# Switcher.net
KiCad netlist of a schematic drawn in Altium Designer
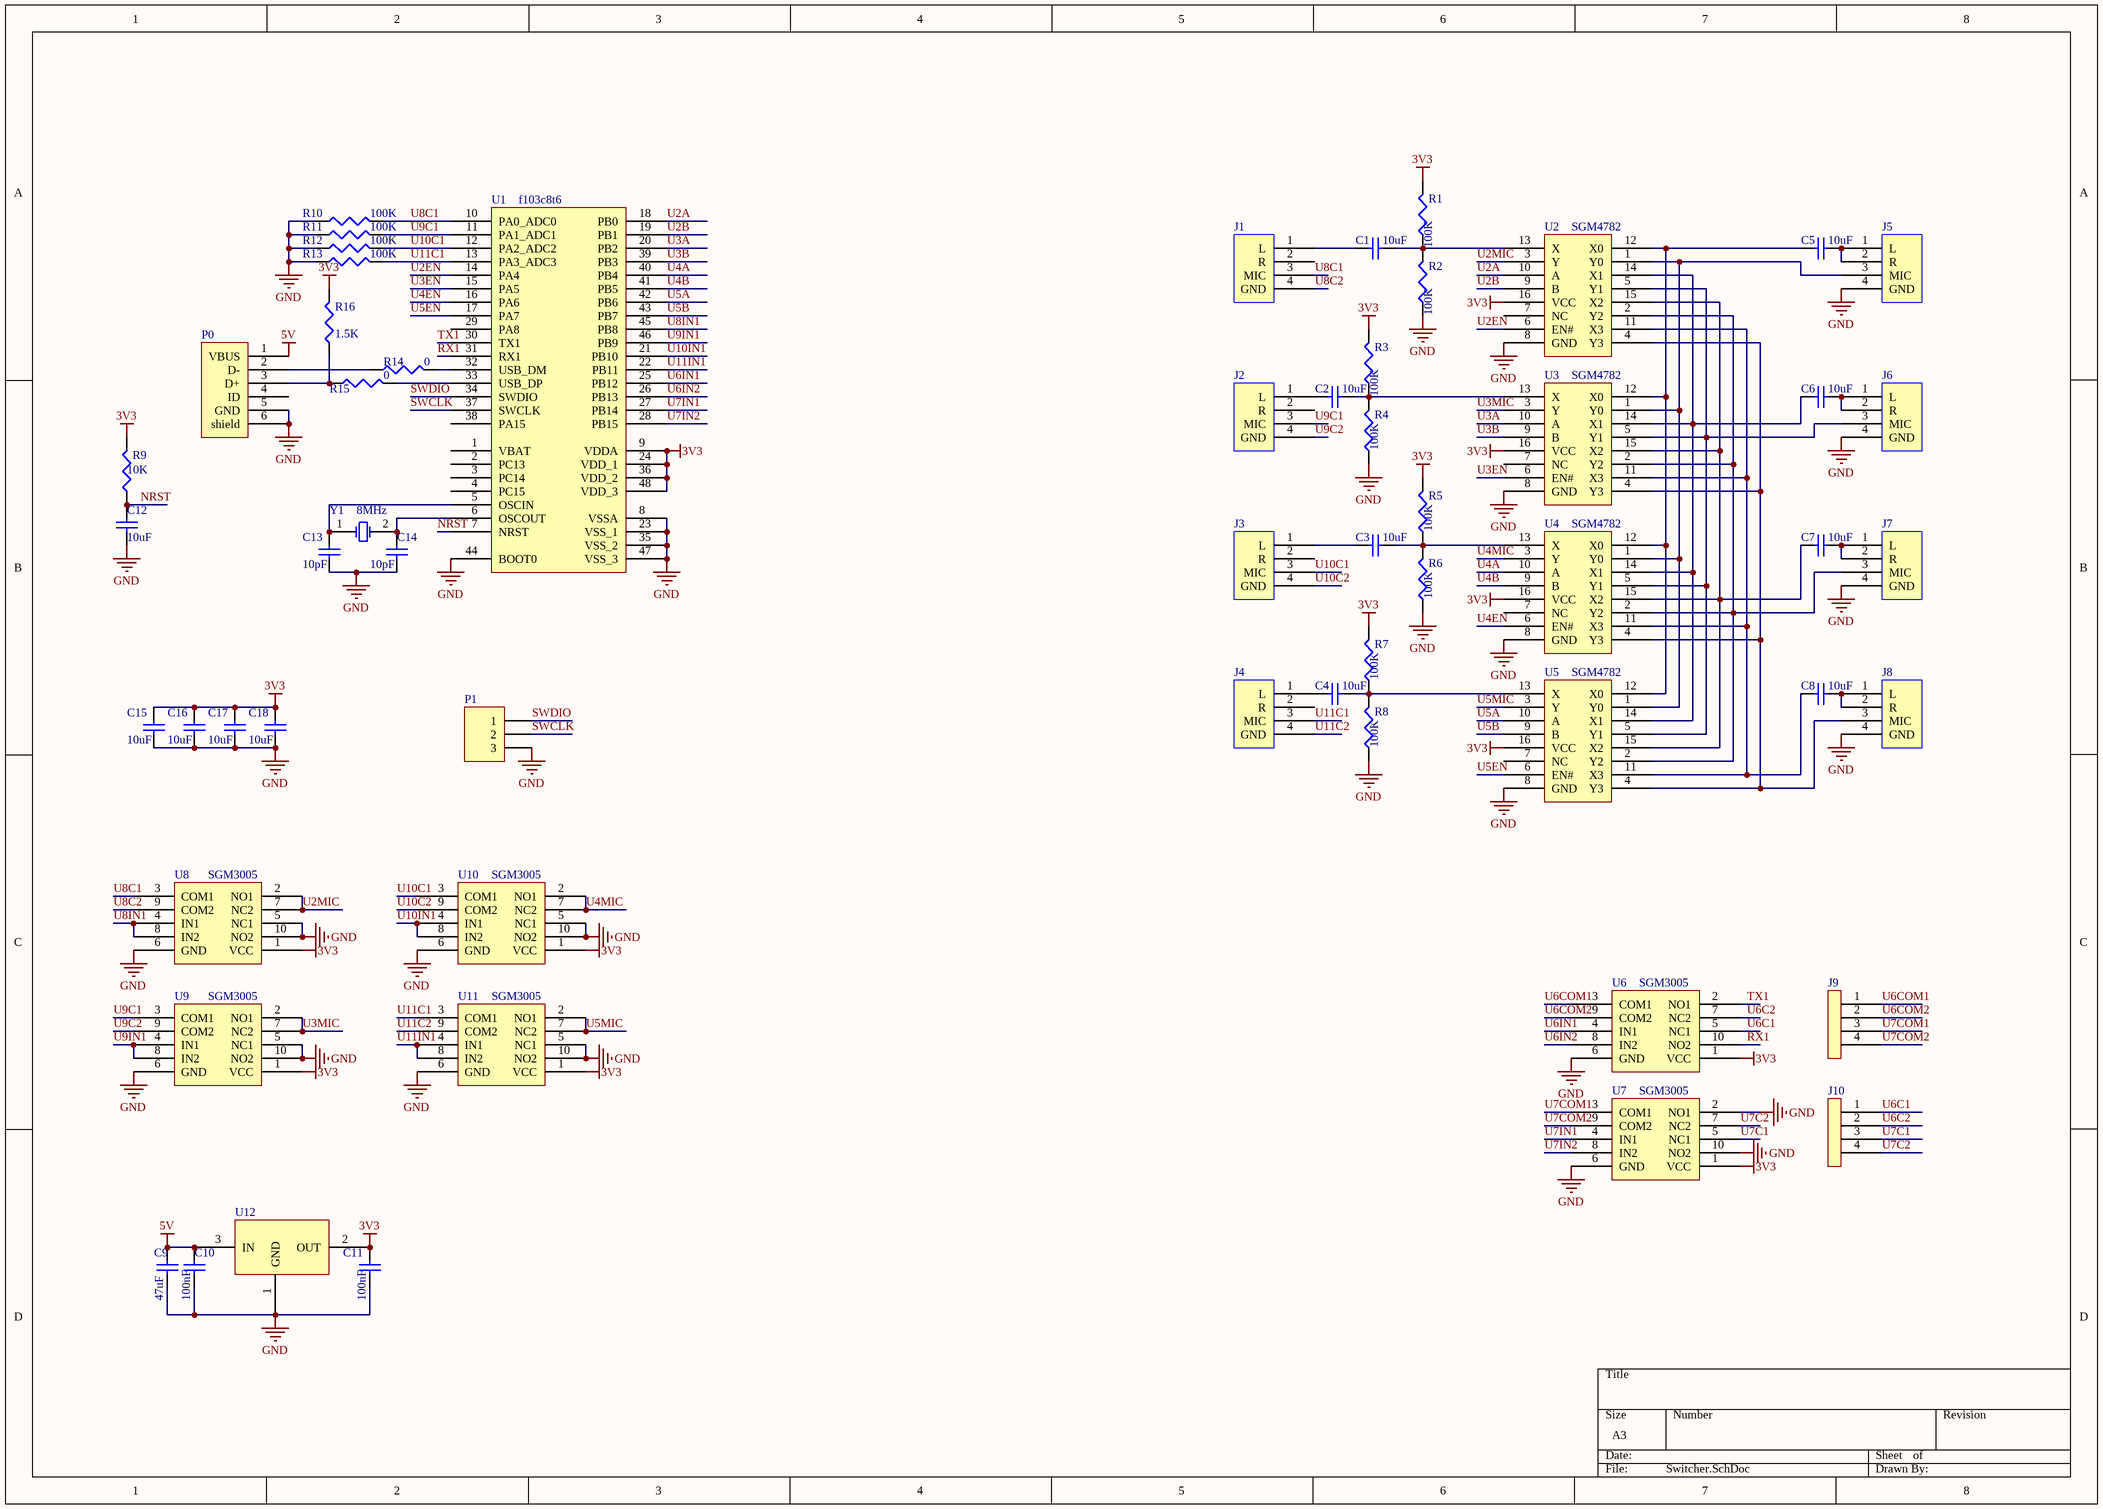
[diagram p0: Switcher.SchDoc]

(export (version "E")
  (design (tool "Eeschema 10.0.6"))
  (components
    (comp (ref "C1")
      (value "10uF")
      (footprint "1608(0603C)")
      (description "Capacitor")
      (fields (field (name "PUBLISHER") "Altium Limited"))
      (libsource (lib "Miscellaneous Devices") (part "Cap"))
    )
    (comp (ref "C2")
      (value "10uF")
      (footprint "1608(0603C)")
      (description "Capacitor")
      (fields (field (name "PUBLISHER") "Altium Limited"))
      (libsource (lib "Miscellaneous Devices") (part "Cap"))
    )
    (comp (ref "C3")
      (value "10uF")
      (footprint "1608(0603C)")
      (description "Capacitor")
      (fields (field (name "PUBLISHER") "Altium Limited"))
      (libsource (lib "Miscellaneous Devices") (part "Cap"))
    )
    (comp (ref "C4")
      (value "10uF")
      (footprint "1608(0603C)")
      (description "Capacitor")
      (fields (field (name "PUBLISHER") "Altium Limited"))
      (libsource (lib "Miscellaneous Devices") (part "Cap"))
    )
    (comp (ref "C5")
      (value "10uF")
      (footprint "1608(0603C)")
      (description "Capacitor")
      (fields (field (name "PUBLISHER") "Altium Limited"))
      (libsource (lib "Miscellaneous Devices") (part "Cap"))
    )
    (comp (ref "C6")
      (value "10uF")
      (footprint "1608(0603C)")
      (description "Capacitor")
      (fields (field (name "PUBLISHER") "Altium Limited"))
      (libsource (lib "Miscellaneous Devices") (part "Cap"))
    )
    (comp (ref "C7")
      (value "10uF")
      (footprint "1608(0603C)")
      (description "Capacitor")
      (fields (field (name "PUBLISHER") "Altium Limited"))
      (libsource (lib "Miscellaneous Devices") (part "Cap"))
    )
    (comp (ref "C8")
      (value "10uF")
      (footprint "1608(0603C)")
      (description "Capacitor")
      (fields (field (name "PUBLISHER") "Altium Limited"))
      (libsource (lib "Miscellaneous Devices") (part "Cap"))
    )
    (comp (ref "C9")
      (value "47uF")
      (footprint "1608(0603C)")
      (description "Capacitor")
      (fields (field (name "PUBLISHER") "Altium Limited"))
      (libsource (lib "Miscellaneous Devices") (part "Cap"))
    )
    (comp (ref "C10")
      (value "100nF")
      (footprint "1608(0603C)")
      (description "Capacitor")
      (fields (field (name "PUBLISHER") "Altium Limited"))
      (libsource (lib "Miscellaneous Devices") (part "Cap"))
    )
    (comp (ref "C11")
      (value "100nF")
      (footprint "1608(0603C)")
      (description "Capacitor")
      (fields (field (name "PUBLISHER") "Altium Limited"))
      (libsource (lib "Miscellaneous Devices") (part "Cap"))
    )
    (comp (ref "C12")
      (value "10uF")
      (footprint "1608(0603C)")
      (description "Capacitor")
      (fields (field (name "PUBLISHER") "Altium Limited"))
      (libsource (lib "Miscellaneous Devices") (part "Cap"))
    )
    (comp (ref "C13")
      (value "10pF")
      (footprint "1608(0603C)")
      (description "Capacitor")
      (fields (field (name "PUBLISHER") "Altium Limited"))
      (libsource (lib "Miscellaneous Devices") (part "Cap"))
    )
    (comp (ref "C14")
      (value "10pF")
      (footprint "1608(0603C)")
      (description "Capacitor")
      (fields (field (name "PUBLISHER") "Altium Limited"))
      (libsource (lib "Miscellaneous Devices") (part "Cap"))
    )
    (comp (ref "C15")
      (value "10uF")
      (footprint "1608(0603C)")
      (description "Capacitor")
      (fields (field (name "PUBLISHER") "Altium Limited"))
      (libsource (lib "Miscellaneous Devices") (part "Cap"))
    )
    (comp (ref "C16")
      (value "10uF")
      (footprint "1608(0603C)")
      (description "Capacitor")
      (fields (field (name "PUBLISHER") "Altium Limited"))
      (libsource (lib "Miscellaneous Devices") (part "Cap"))
    )
    (comp (ref "C17")
      (value "10uF")
      (footprint "1608(0603C)")
      (description "Capacitor")
      (fields (field (name "PUBLISHER") "Altium Limited"))
      (libsource (lib "Miscellaneous Devices") (part "Cap"))
    )
    (comp (ref "C18")
      (value "10uF")
      (footprint "1608(0603C)")
      (description "Capacitor")
      (fields (field (name "PUBLISHER") "Altium Limited"))
      (libsource (lib "Miscellaneous Devices") (part "Cap"))
    )
    (comp (ref "J1") (value "~") (footprint "PJ-322") (libsource (lib "Switcher") (part "seg-4")))
    (comp (ref "J2") (value "~") (footprint "PJ-322") (libsource (lib "Switcher") (part "seg-4")))
    (comp (ref "J3") (value "~") (footprint "PJ-322") (libsource (lib "Switcher") (part "seg-4")))
    (comp (ref "J4") (value "~") (footprint "PJ-322") (libsource (lib "Switcher") (part "seg-4")))
    (comp (ref "J5")
      (value "~")
      (footprint "PJ-322")
      (description "OMTP")
      (libsource (lib "") (part "seg-4_1"))
    )
    (comp (ref "J6") (value "~") (footprint "PJ-322") (libsource (lib "") (part "seg-4_1")))
    (comp (ref "J7") (value "~") (footprint "PJ-322") (libsource (lib "") (part "seg-4_1")))
    (comp (ref "J8") (value "~") (footprint "PJ-322") (libsource (lib "") (part "seg-4_1")))
    (comp (ref "J9") (value "~") (footprint "PJ-322") (libsource (lib "Switcher") (part "CON4")))
    (comp (ref "J10") (value "~") (footprint "PJ-322") (libsource (lib "Switcher") (part "CON4")))
    (comp (ref "P0") (value "~") (footprint "USB_MICRO") (libsource (lib "Switcher") (part "micro_usb")))
    (comp (ref "P1")
      (value "~")
      (footprint "SIP3")
      (description "Header, 3-Pin")
      (fields (field (name "PUBLISHER") "Altium Limited"))
      (libsource (lib "Miscellaneous Connectors") (part "Header 3"))
    )
    (comp (ref "R1")
      (value "100K")
      (footprint "1608(0603R)")
      (description "Resistor")
      (fields (field (name "PUBLISHER") "Altium Limited"))
      (libsource (lib "Miscellaneous Devices") (part "Res3"))
    )
    (comp (ref "R2")
      (value "100K")
      (footprint "1608(0603R)")
      (description "Resistor")
      (fields (field (name "PUBLISHER") "Altium Limited"))
      (libsource (lib "Miscellaneous Devices") (part "Res3"))
    )
    (comp (ref "R3")
      (value "100K")
      (footprint "1608(0603R)")
      (description "Resistor")
      (fields (field (name "PUBLISHER") "Altium Limited"))
      (libsource (lib "Miscellaneous Devices") (part "Res3"))
    )
    (comp (ref "R4")
      (value "100K")
      (footprint "1608(0603R)")
      (description "Resistor")
      (fields (field (name "PUBLISHER") "Altium Limited"))
      (libsource (lib "Miscellaneous Devices") (part "Res3"))
    )
    (comp (ref "R5")
      (value "100K")
      (footprint "1608(0603R)")
      (description "Resistor")
      (fields (field (name "PUBLISHER") "Altium Limited"))
      (libsource (lib "Miscellaneous Devices") (part "Res3"))
    )
    (comp (ref "R6")
      (value "100K")
      (footprint "1608(0603R)")
      (description "Resistor")
      (fields (field (name "PUBLISHER") "Altium Limited"))
      (libsource (lib "Miscellaneous Devices") (part "Res3"))
    )
    (comp (ref "R7")
      (value "100K")
      (footprint "1608(0603R)")
      (description "Resistor")
      (fields (field (name "PUBLISHER") "Altium Limited"))
      (libsource (lib "Miscellaneous Devices") (part "Res3"))
    )
    (comp (ref "R8")
      (value "100K")
      (footprint "1608(0603R)")
      (description "Resistor")
      (fields (field (name "PUBLISHER") "Altium Limited"))
      (libsource (lib "Miscellaneous Devices") (part "Res3"))
    )
    (comp (ref "R9")
      (value "10K")
      (footprint "1608(0603R)")
      (description "Resistor")
      (fields (field (name "PUBLISHER") "Altium Limited"))
      (libsource (lib "Miscellaneous Devices") (part "Res3"))
    )
    (comp (ref "R10")
      (value "100K")
      (footprint "1608(0603R)")
      (description "Resistor")
      (fields (field (name "PUBLISHER") "Altium Limited"))
      (libsource (lib "Miscellaneous Devices") (part "Res3"))
    )
    (comp (ref "R11")
      (value "100K")
      (footprint "1608(0603R)")
      (description "Resistor")
      (fields (field (name "PUBLISHER") "Altium Limited"))
      (libsource (lib "Miscellaneous Devices") (part "Res3"))
    )
    (comp (ref "R12")
      (value "100K")
      (footprint "1608(0603R)")
      (description "Resistor")
      (fields (field (name "PUBLISHER") "Altium Limited"))
      (libsource (lib "Miscellaneous Devices") (part "Res3"))
    )
    (comp (ref "R13")
      (value "100K")
      (footprint "1608(0603R)")
      (description "Resistor")
      (fields (field (name "PUBLISHER") "Altium Limited"))
      (libsource (lib "Miscellaneous Devices") (part "Res3"))
    )
    (comp (ref "R14")
      (value "0")
      (footprint "1608(0603R)")
      (description "Resistor")
      (fields (field (name "PUBLISHER") "Altium Limited"))
      (libsource (lib "Miscellaneous Devices") (part "Res3"))
    )
    (comp (ref "R15")
      (value "0")
      (footprint "1608(0603R)")
      (description "Resistor")
      (fields (field (name "PUBLISHER") "Altium Limited"))
      (libsource (lib "Miscellaneous Devices") (part "Res3"))
    )
    (comp (ref "R16")
      (value "1.5K")
      (footprint "1608(0603R)")
      (description "Resistor")
      (fields (field (name "PUBLISHER") "Altium Limited"))
      (libsource (lib "Miscellaneous Devices") (part "Res3"))
    )
    (comp (ref "U1") (value "f103c8t6") (footprint "LQFP48") (libsource (lib "Switcher") (part "f103c8t6")))
    (comp (ref "U2") (value "SGM4782") (footprint "TSSOP-16") (libsource (lib "Switcher") (part "SGM4782")))
    (comp (ref "U3") (value "SGM4782") (footprint "TSSOP-16") (libsource (lib "Switcher") (part "SGM4782")))
    (comp (ref "U4") (value "SGM4782") (footprint "TSSOP-16") (libsource (lib "Switcher") (part "SGM4782")))
    (comp (ref "U5") (value "SGM4782") (footprint "TSSOP-16") (libsource (lib "Switcher") (part "SGM4782")))
    (comp (ref "U6") (value "SGM3005") (footprint "MSOP-10") (libsource (lib "Switcher") (part "SGM3005")))
    (comp (ref "U7") (value "SGM3005") (footprint "MSOP-10") (libsource (lib "Switcher") (part "SGM3005")))
    (comp (ref "U8") (value "SGM3005") (footprint "MSOP-10") (libsource (lib "Switcher") (part "SGM3005")))
    (comp (ref "U9") (value "SGM3005") (footprint "MSOP-10") (libsource (lib "Switcher") (part "SGM3005")))
    (comp (ref "U10") (value "SGM3005") (footprint "MSOP-10") (libsource (lib "Switcher") (part "SGM3005")))
    (comp (ref "U11") (value "SGM3005") (footprint "MSOP-10") (libsource (lib "Switcher") (part "SGM3005")))
    (comp (ref "U12") (value "~") (footprint "SOT-223") (libsource (lib "Switcher") (part "ASM1117-3.3")))
    (comp (ref "Y1")
      (value "8MHz")
      (footprint "XTAL1")
      (description "Crystal Oscillator")
      (fields (field (name "PUBLISHER") "Altium Limited"))
      (libsource (lib "Miscellaneous Devices") (part "XTAL"))
    )
  )
  (nets
    (net (code "1") (name "/NRST") (class "Default")
      (node (ref "C12") (pin "2") (pinfunction "2_2") (pintype "passive"))
      (node (ref "R9") (pin "1") (pinfunction "1_1") (pintype "passive"))
      (node (ref "U1") (pin "7") (pinfunction "NRST_7") (pintype "passive"))
    )
    (net (code "2") (name "/RX1") (class "Default")
      (node (ref "U1") (pin "31") (pinfunction "RX1_31") (pintype "passive"))
      (node (ref "U6") (pin "10") (pinfunction "NO2_10") (pintype "passive"))
    )
    (net (code "3") (name "/SWCLK") (class "Default")
      (node (ref "P1") (pin "2") (pinfunction "2_2") (pintype "passive"))
      (node (ref "U1") (pin "37") (pinfunction "SWCLK_37") (pintype "passive"))
    )
    (net (code "4") (name "/SWDIO") (class "Default")
      (node (ref "P1") (pin "1") (pinfunction "1_1") (pintype "passive"))
      (node (ref "U1") (pin "34") (pinfunction "SWDIO_34") (pintype "passive"))
    )
    (net (code "5") (name "/TX1") (class "Default")
      (node (ref "U1") (pin "30") (pinfunction "TX1_30") (pintype "passive"))
      (node (ref "U6") (pin "2") (pinfunction "NO1_2") (pintype "passive"))
    )
    (net (code "6") (name "/U2A") (class "Default")
      (node (ref "U1") (pin "18") (pinfunction "PB0_18") (pintype "passive"))
      (node (ref "U2") (pin "10") (pinfunction "A_10") (pintype "passive"))
    )
    (net (code "7") (name "/U2B") (class "Default")
      (node (ref "U1") (pin "19") (pinfunction "PB1_19") (pintype "passive"))
      (node (ref "U2") (pin "9") (pinfunction "B_9") (pintype "passive"))
    )
    (net (code "8") (name "/U2EN") (class "Default")
      (node (ref "U1") (pin "14") (pinfunction "PA4_14") (pintype "passive"))
      (node (ref "U2") (pin "6") (pinfunction "EN#_6") (pintype "passive"))
    )
    (net (code "9") (name "/U2MIC") (class "Default")
      (node (ref "U2") (pin "3") (pinfunction "Y_3") (pintype "passive"))
      (node (ref "U8") (pin "2") (pinfunction "NO1_2") (pintype "passive"))
      (node (ref "U8") (pin "7") (pinfunction "NC2_7") (pintype "passive"))
    )
    (net (code "10") (name "/U3A") (class "Default")
      (node (ref "U1") (pin "20") (pinfunction "PB2_20") (pintype "passive"))
      (node (ref "U3") (pin "10") (pinfunction "A_10") (pintype "passive"))
    )
    (net (code "11") (name "/U3B") (class "Default")
      (node (ref "U1") (pin "39") (pinfunction "PB3_39") (pintype "passive"))
      (node (ref "U3") (pin "9") (pinfunction "B_9") (pintype "passive"))
    )
    (net (code "12") (name "/U3EN") (class "Default")
      (node (ref "U1") (pin "15") (pinfunction "PA5_15") (pintype "passive"))
      (node (ref "U3") (pin "6") (pinfunction "EN#_6") (pintype "passive"))
    )
    (net (code "13") (name "/U3MIC") (class "Default")
      (node (ref "U3") (pin "3") (pinfunction "Y_3") (pintype "passive"))
      (node (ref "U9") (pin "2") (pinfunction "NO1_2") (pintype "passive"))
      (node (ref "U9") (pin "7") (pinfunction "NC2_7") (pintype "passive"))
    )
    (net (code "14") (name "/U4A") (class "Default")
      (node (ref "U1") (pin "40") (pinfunction "PB4_40") (pintype "passive"))
      (node (ref "U4") (pin "10") (pinfunction "A_10") (pintype "passive"))
    )
    (net (code "15") (name "/U4B") (class "Default")
      (node (ref "U1") (pin "41") (pinfunction "PB5_41") (pintype "passive"))
      (node (ref "U4") (pin "9") (pinfunction "B_9") (pintype "passive"))
    )
    (net (code "16") (name "/U4EN") (class "Default")
      (node (ref "U1") (pin "16") (pinfunction "PA6_16") (pintype "passive"))
      (node (ref "U4") (pin "6") (pinfunction "EN#_6") (pintype "passive"))
    )
    (net (code "17") (name "/U4MIC") (class "Default")
      (node (ref "U10") (pin "2") (pinfunction "NO1_2") (pintype "passive"))
      (node (ref "U10") (pin "7") (pinfunction "NC2_7") (pintype "passive"))
      (node (ref "U4") (pin "3") (pinfunction "Y_3") (pintype "passive"))
    )
    (net (code "18") (name "/U5A") (class "Default")
      (node (ref "U1") (pin "42") (pinfunction "PB6_42") (pintype "passive"))
      (node (ref "U5") (pin "10") (pinfunction "A_10") (pintype "passive"))
    )
    (net (code "19") (name "/U5B") (class "Default")
      (node (ref "U1") (pin "43") (pinfunction "PB7_43") (pintype "passive"))
      (node (ref "U5") (pin "9") (pinfunction "B_9") (pintype "passive"))
    )
    (net (code "20") (name "/U5EN") (class "Default")
      (node (ref "U1") (pin "17") (pinfunction "PA7_17") (pintype "passive"))
      (node (ref "U5") (pin "6") (pinfunction "EN#_6") (pintype "passive"))
    )
    (net (code "21") (name "/U5MIC") (class "Default")
      (node (ref "U11") (pin "2") (pinfunction "NO1_2") (pintype "passive"))
      (node (ref "U11") (pin "7") (pinfunction "NC2_7") (pintype "passive"))
      (node (ref "U5") (pin "3") (pinfunction "Y_3") (pintype "passive"))
    )
    (net (code "22") (name "/U6C1") (class "Default")
      (node (ref "J10") (pin "1") (pintype "passive"))
      (node (ref "U6") (pin "5") (pinfunction "NC1_5") (pintype "passive"))
    )
    (net (code "23") (name "/U6C2") (class "Default")
      (node (ref "J10") (pin "2") (pintype "passive"))
      (node (ref "U6") (pin "7") (pinfunction "NC2_7") (pintype "passive"))
    )
    (net (code "24") (name "/U6COM1") (class "Default")
      (node (ref "J9") (pin "1") (pintype "passive"))
      (node (ref "U6") (pin "3") (pinfunction "COM1_3") (pintype "passive"))
    )
    (net (code "25") (name "/U6COM2") (class "Default")
      (node (ref "J9") (pin "2") (pintype "passive"))
      (node (ref "U6") (pin "9") (pinfunction "COM2_9") (pintype "passive"))
    )
    (net (code "26") (name "/U6IN1") (class "Default")
      (node (ref "U1") (pin "25") (pinfunction "PB12_25") (pintype "passive"))
      (node (ref "U6") (pin "4") (pinfunction "IN1_4") (pintype "passive"))
    )
    (net (code "27") (name "/U6IN2") (class "Default")
      (node (ref "U1") (pin "26") (pinfunction "PB13_26") (pintype "passive"))
      (node (ref "U6") (pin "8") (pinfunction "IN2_8") (pintype "passive"))
    )
    (net (code "28") (name "/U7C1") (class "Default")
      (node (ref "J10") (pin "3") (pintype "passive"))
      (node (ref "U7") (pin "5") (pinfunction "NC1_5") (pintype "passive"))
    )
    (net (code "29") (name "/U7C2") (class "Default")
      (node (ref "J10") (pin "4") (pintype "passive"))
      (node (ref "U7") (pin "7") (pinfunction "NC2_7") (pintype "passive"))
    )
    (net (code "30") (name "/U7COM1") (class "Default")
      (node (ref "J9") (pin "3") (pintype "passive"))
      (node (ref "U7") (pin "3") (pinfunction "COM1_3") (pintype "passive"))
    )
    (net (code "31") (name "/U7COM2") (class "Default")
      (node (ref "J9") (pin "4") (pintype "passive"))
      (node (ref "U7") (pin "9") (pinfunction "COM2_9") (pintype "passive"))
    )
    (net (code "32") (name "/U7IN1") (class "Default")
      (node (ref "U1") (pin "27") (pinfunction "PB14_27") (pintype "passive"))
      (node (ref "U7") (pin "4") (pinfunction "IN1_4") (pintype "passive"))
    )
    (net (code "33") (name "/U7IN2") (class "Default")
      (node (ref "U1") (pin "28") (pinfunction "PB15_28") (pintype "passive"))
      (node (ref "U7") (pin "8") (pinfunction "IN2_8") (pintype "passive"))
    )
    (net (code "34") (name "/U8C1") (class "Default")
      (node (ref "J1") (pin "3") (pinfunction "MIC_3") (pintype "passive"))
      (node (ref "R10") (pin "2") (pinfunction "2_2") (pintype "passive"))
      (node (ref "U1") (pin "10") (pinfunction "PA0_ADC0_10") (pintype "passive"))
      (node (ref "U8") (pin "3") (pinfunction "COM1_3") (pintype "passive"))
    )
    (net (code "35") (name "/U8C2") (class "Default")
      (node (ref "J1") (pin "4") (pinfunction "GND_4") (pintype "passive"))
      (node (ref "U8") (pin "9") (pinfunction "COM2_9") (pintype "passive"))
    )
    (net (code "36") (name "/U8IN1") (class "Default")
      (node (ref "U1") (pin "45") (pinfunction "PB8_45") (pintype "passive"))
      (node (ref "U8") (pin "4") (pinfunction "IN1_4") (pintype "passive"))
      (node (ref "U8") (pin "8") (pinfunction "IN2_8") (pintype "passive"))
    )
    (net (code "37") (name "/U9C1") (class "Default")
      (node (ref "J2") (pin "3") (pinfunction "MIC_3") (pintype "passive"))
      (node (ref "R11") (pin "2") (pinfunction "2_2") (pintype "passive"))
      (node (ref "U1") (pin "11") (pinfunction "PA1_ADC1_11") (pintype "passive"))
      (node (ref "U9") (pin "3") (pinfunction "COM1_3") (pintype "passive"))
    )
    (net (code "38") (name "/U9C2") (class "Default")
      (node (ref "J2") (pin "4") (pinfunction "GND_4") (pintype "passive"))
      (node (ref "U9") (pin "9") (pinfunction "COM2_9") (pintype "passive"))
    )
    (net (code "39") (name "/U9IN1") (class "Default")
      (node (ref "U1") (pin "46") (pinfunction "PB9_46") (pintype "passive"))
      (node (ref "U9") (pin "4") (pinfunction "IN1_4") (pintype "passive"))
      (node (ref "U9") (pin "8") (pinfunction "IN2_8") (pintype "passive"))
    )
    (net (code "40") (name "/U10C1") (class "Default")
      (node (ref "J3") (pin "3") (pinfunction "MIC_3") (pintype "passive"))
      (node (ref "R12") (pin "2") (pinfunction "2_2") (pintype "passive"))
      (node (ref "U1") (pin "12") (pinfunction "PA2_ADC2_12") (pintype "passive"))
      (node (ref "U10") (pin "3") (pinfunction "COM1_3") (pintype "passive"))
    )
    (net (code "41") (name "/U10C2") (class "Default")
      (node (ref "J3") (pin "4") (pinfunction "GND_4") (pintype "passive"))
      (node (ref "U10") (pin "9") (pinfunction "COM2_9") (pintype "passive"))
    )
    (net (code "42") (name "/U10IN1") (class "Default")
      (node (ref "U1") (pin "21") (pinfunction "PB10_21") (pintype "passive"))
      (node (ref "U10") (pin "4") (pinfunction "IN1_4") (pintype "passive"))
      (node (ref "U10") (pin "8") (pinfunction "IN2_8") (pintype "passive"))
    )
    (net (code "43") (name "/U11C1") (class "Default")
      (node (ref "J4") (pin "3") (pinfunction "MIC_3") (pintype "passive"))
      (node (ref "R13") (pin "2") (pinfunction "2_2") (pintype "passive"))
      (node (ref "U1") (pin "13") (pinfunction "PA3_ADC3_13") (pintype "passive"))
      (node (ref "U11") (pin "3") (pinfunction "COM1_3") (pintype "passive"))
    )
    (net (code "44") (name "/U11C2") (class "Default")
      (node (ref "J4") (pin "4") (pinfunction "GND_4") (pintype "passive"))
      (node (ref "U11") (pin "9") (pinfunction "COM2_9") (pintype "passive"))
    )
    (net (code "45") (name "/U11IN1") (class "Default")
      (node (ref "U1") (pin "22") (pinfunction "PB11_22") (pintype "passive"))
      (node (ref "U11") (pin "4") (pinfunction "IN1_4") (pintype "passive"))
      (node (ref "U11") (pin "8") (pinfunction "IN2_8") (pintype "passive"))
    )
    (net (code "46") (name "3V3") (class "Default")
      (node (ref "C11") (pin "2") (pinfunction "2_2") (pintype "passive"))
      (node (ref "C15") (pin "2") (pinfunction "2_2") (pintype "passive"))
      (node (ref "C16") (pin "2") (pinfunction "2_2") (pintype "passive"))
      (node (ref "C17") (pin "2") (pinfunction "2_2") (pintype "passive"))
      (node (ref "C18") (pin "2") (pinfunction "2_2") (pintype "passive"))
      (node (ref "R1") (pin "2") (pinfunction "2_2") (pintype "passive"))
      (node (ref "R16") (pin "2") (pinfunction "2_2") (pintype "passive"))
      (node (ref "R3") (pin "2") (pinfunction "2_2") (pintype "passive"))
      (node (ref "R5") (pin "2") (pinfunction "2_2") (pintype "passive"))
      (node (ref "R7") (pin "2") (pinfunction "2_2") (pintype "passive"))
      (node (ref "R9") (pin "2") (pinfunction "2_2") (pintype "passive"))
      (node (ref "U1") (pin "24") (pinfunction "VDD_1_24") (pintype "passive"))
      (node (ref "U1") (pin "36") (pinfunction "VDD_2_36") (pintype "passive"))
      (node (ref "U1") (pin "48") (pinfunction "VDD_3_48") (pintype "passive"))
      (node (ref "U1") (pin "9") (pinfunction "VDDA_9") (pintype "passive"))
      (node (ref "U10") (pin "1") (pinfunction "VCC_1") (pintype "passive"))
      (node (ref "U11") (pin "1") (pinfunction "VCC_1") (pintype "passive"))
      (node (ref "U12") (pin "2") (pinfunction "OUT_2") (pintype "passive"))
      (node (ref "U2") (pin "16") (pinfunction "VCC_16") (pintype "passive"))
      (node (ref "U3") (pin "16") (pinfunction "VCC_16") (pintype "passive"))
      (node (ref "U4") (pin "16") (pinfunction "VCC_16") (pintype "passive"))
      (node (ref "U5") (pin "16") (pinfunction "VCC_16") (pintype "passive"))
      (node (ref "U6") (pin "1") (pinfunction "VCC_1") (pintype "passive"))
      (node (ref "U7") (pin "1") (pinfunction "VCC_1") (pintype "passive"))
      (node (ref "U8") (pin "1") (pinfunction "VCC_1") (pintype "passive"))
      (node (ref "U9") (pin "1") (pinfunction "VCC_1") (pintype "passive"))
    )
    (net (code "47") (name "5V") (class "Default")
      (node (ref "C10") (pin "2") (pinfunction "2_2") (pintype "passive"))
      (node (ref "C9") (pin "2") (pinfunction "2_2") (pintype "passive"))
      (node (ref "P0") (pin "1") (pinfunction "VBUS_1") (pintype "passive"))
      (node (ref "U12") (pin "3") (pinfunction "IN_3") (pintype "passive"))
    )
    (net (code "48") (name "GND") (class "Default")
      (node (ref "C10") (pin "1") (pinfunction "1_1") (pintype "passive"))
      (node (ref "C11") (pin "1") (pinfunction "1_1") (pintype "passive"))
      (node (ref "C12") (pin "1") (pinfunction "1_1") (pintype "passive"))
      (node (ref "C13") (pin "1") (pinfunction "1_1") (pintype "passive"))
      (node (ref "C14") (pin "1") (pinfunction "1_1") (pintype "passive"))
      (node (ref "C15") (pin "1") (pinfunction "1_1") (pintype "passive"))
      (node (ref "C16") (pin "1") (pinfunction "1_1") (pintype "passive"))
      (node (ref "C17") (pin "1") (pinfunction "1_1") (pintype "passive"))
      (node (ref "C18") (pin "1") (pinfunction "1_1") (pintype "passive"))
      (node (ref "C9") (pin "1") (pinfunction "1_1") (pintype "passive"))
      (node (ref "J5") (pin "4") (pinfunction "GND_4") (pintype "passive"))
      (node (ref "J6") (pin "4") (pinfunction "GND_4") (pintype "passive"))
      (node (ref "J7") (pin "4") (pinfunction "GND_4") (pintype "passive"))
      (node (ref "J8") (pin "4") (pinfunction "GND_4") (pintype "passive"))
      (node (ref "P0") (pin "5") (pinfunction "GND_5") (pintype "passive"))
      (node (ref "P0") (pin "6") (pinfunction "shield_6") (pintype "passive"))
      (node (ref "P1") (pin "3") (pinfunction "3_3") (pintype "passive"))
      (node (ref "R10") (pin "1") (pinfunction "1_1") (pintype "passive"))
      (node (ref "R11") (pin "1") (pinfunction "1_1") (pintype "passive"))
      (node (ref "R12") (pin "1") (pinfunction "1_1") (pintype "passive"))
      (node (ref "R13") (pin "1") (pinfunction "1_1") (pintype "passive"))
      (node (ref "R2") (pin "1") (pinfunction "1_1") (pintype "passive"))
      (node (ref "R4") (pin "1") (pinfunction "1_1") (pintype "passive"))
      (node (ref "R6") (pin "1") (pinfunction "1_1") (pintype "passive"))
      (node (ref "R8") (pin "1") (pinfunction "1_1") (pintype "passive"))
      (node (ref "U1") (pin "23") (pinfunction "VSS_1_23") (pintype "passive"))
      (node (ref "U1") (pin "35") (pinfunction "VSS_2_35") (pintype "passive"))
      (node (ref "U1") (pin "44") (pinfunction "BOOT0_44") (pintype "passive"))
      (node (ref "U1") (pin "47") (pinfunction "VSS_3_47") (pintype "passive"))
      (node (ref "U1") (pin "8") (pinfunction "VSSA_8") (pintype "passive"))
      (node (ref "U10") (pin "10") (pinfunction "NO2_10") (pintype "passive"))
      (node (ref "U10") (pin "5") (pinfunction "NC1_5") (pintype "passive"))
      (node (ref "U10") (pin "6") (pinfunction "GND_6") (pintype "passive"))
      (node (ref "U11") (pin "10") (pinfunction "NO2_10") (pintype "passive"))
      (node (ref "U11") (pin "5") (pinfunction "NC1_5") (pintype "passive"))
      (node (ref "U11") (pin "6") (pinfunction "GND_6") (pintype "passive"))
      (node (ref "U12") (pin "1") (pinfunction "GND_1") (pintype "passive"))
      (node (ref "U2") (pin "8") (pinfunction "GND_8") (pintype "passive"))
      (node (ref "U3") (pin "8") (pinfunction "GND_8") (pintype "passive"))
      (node (ref "U4") (pin "8") (pinfunction "GND_8") (pintype "passive"))
      (node (ref "U5") (pin "8") (pinfunction "GND_8") (pintype "passive"))
      (node (ref "U6") (pin "6") (pinfunction "GND_6") (pintype "passive"))
      (node (ref "U7") (pin "10") (pinfunction "NO2_10") (pintype "passive"))
      (node (ref "U7") (pin "2") (pinfunction "NO1_2") (pintype "passive"))
      (node (ref "U7") (pin "6") (pinfunction "GND_6") (pintype "passive"))
      (node (ref "U8") (pin "10") (pinfunction "NO2_10") (pintype "passive"))
      (node (ref "U8") (pin "5") (pinfunction "NC1_5") (pintype "passive"))
      (node (ref "U8") (pin "6") (pinfunction "GND_6") (pintype "passive"))
      (node (ref "U9") (pin "10") (pinfunction "NO2_10") (pintype "passive"))
      (node (ref "U9") (pin "5") (pinfunction "NC1_5") (pintype "passive"))
      (node (ref "U9") (pin "6") (pinfunction "GND_6") (pintype "passive"))
    )
    (net (code "49") (name "Net-(J1-L)") (class "Default")
      (node (ref "C1") (pin "1") (pinfunction "1_1") (pintype "passive"))
      (node (ref "J1") (pin "1") (pinfunction "L_1") (pintype "passive"))
    )
    (net (code "50") (name "Net-(J2-L)") (class "Default")
      (node (ref "C2") (pin "1") (pinfunction "1_1") (pintype "passive"))
      (node (ref "J2") (pin "1") (pinfunction "L_1") (pintype "passive"))
    )
    (net (code "51") (name "Net-(J3-L)") (class "Default")
      (node (ref "C3") (pin "1") (pinfunction "1_1") (pintype "passive"))
      (node (ref "J3") (pin "1") (pinfunction "L_1") (pintype "passive"))
    )
    (net (code "52") (name "Net-(J4-L)") (class "Default")
      (node (ref "C4") (pin "1") (pinfunction "1_1") (pintype "passive"))
      (node (ref "J4") (pin "1") (pinfunction "L_1") (pintype "passive"))
    )
    (net (code "53") (name "Net-(J5-L)") (class "Default")
      (node (ref "C5") (pin "2") (pinfunction "2_2") (pintype "passive"))
      (node (ref "J5") (pin "1") (pinfunction "L_1") (pintype "passive"))
      (node (ref "J5") (pin "2") (pinfunction "R_2") (pintype "passive"))
    )
    (net (code "54") (name "Net-(J5-MIC)") (class "Default")
      (node (ref "J5") (pin "3") (pinfunction "MIC_3") (pintype "passive"))
      (node (ref "U2") (pin "1") (pinfunction "Y0_1") (pintype "passive"))
      (node (ref "U3") (pin "1") (pinfunction "Y0_1") (pintype "passive"))
      (node (ref "U4") (pin "1") (pinfunction "Y0_1") (pintype "passive"))
      (node (ref "U5") (pin "1") (pinfunction "Y0_1") (pintype "passive"))
    )
    (net (code "55") (name "Net-(J6-L)") (class "Default")
      (node (ref "C6") (pin "2") (pinfunction "2_2") (pintype "passive"))
      (node (ref "J6") (pin "1") (pinfunction "L_1") (pintype "passive"))
      (node (ref "J6") (pin "2") (pinfunction "R_2") (pintype "passive"))
    )
    (net (code "56") (name "Net-(J6-MIC)") (class "Default")
      (node (ref "J6") (pin "3") (pinfunction "MIC_3") (pintype "passive"))
      (node (ref "U2") (pin "5") (pinfunction "Y1_5") (pintype "passive"))
      (node (ref "U3") (pin "5") (pinfunction "Y1_5") (pintype "passive"))
      (node (ref "U4") (pin "5") (pinfunction "Y1_5") (pintype "passive"))
      (node (ref "U5") (pin "5") (pinfunction "Y1_5") (pintype "passive"))
    )
    (net (code "57") (name "Net-(J7-L)") (class "Default")
      (node (ref "C7") (pin "2") (pinfunction "2_2") (pintype "passive"))
      (node (ref "J7") (pin "1") (pinfunction "L_1") (pintype "passive"))
      (node (ref "J7") (pin "2") (pinfunction "R_2") (pintype "passive"))
    )
    (net (code "58") (name "Net-(J7-MIC)") (class "Default")
      (node (ref "J7") (pin "3") (pinfunction "MIC_3") (pintype "passive"))
      (node (ref "U2") (pin "2") (pinfunction "Y2_2") (pintype "passive"))
      (node (ref "U3") (pin "2") (pinfunction "Y2_2") (pintype "passive"))
      (node (ref "U4") (pin "2") (pinfunction "Y2_2") (pintype "passive"))
      (node (ref "U5") (pin "2") (pinfunction "Y2_2") (pintype "passive"))
    )
    (net (code "59") (name "Net-(J8-L)") (class "Default")
      (node (ref "C8") (pin "2") (pinfunction "2_2") (pintype "passive"))
      (node (ref "J8") (pin "1") (pinfunction "L_1") (pintype "passive"))
      (node (ref "J8") (pin "2") (pinfunction "R_2") (pintype "passive"))
    )
    (net (code "60") (name "Net-(J8-MIC)") (class "Default")
      (node (ref "J8") (pin "3") (pinfunction "MIC_3") (pintype "passive"))
      (node (ref "U2") (pin "4") (pinfunction "Y3_4") (pintype "passive"))
      (node (ref "U3") (pin "4") (pinfunction "Y3_4") (pintype "passive"))
      (node (ref "U4") (pin "4") (pinfunction "Y3_4") (pintype "passive"))
      (node (ref "U5") (pin "4") (pinfunction "Y3_4") (pintype "passive"))
    )
    (net (code "61") (name "Net-(P0-D+)") (class "Default")
      (node (ref "P0") (pin "3") (pinfunction "D+_3") (pintype "passive"))
      (node (ref "R15") (pin "1") (pinfunction "1_1") (pintype "passive"))
      (node (ref "R16") (pin "1") (pinfunction "1_1") (pintype "passive"))
    )
    (net (code "62") (name "Net-(P0-D-)") (class "Default")
      (node (ref "P0") (pin "2") (pinfunction "D-_2") (pintype "passive"))
      (node (ref "R14") (pin "1") (pinfunction "1_1") (pintype "passive"))
    )
    (net (code "63") (name "Net-(U1-OSCIN)") (class "Default")
      (node (ref "C13") (pin "2") (pinfunction "2_2") (pintype "passive"))
      (node (ref "U1") (pin "5") (pinfunction "OSCIN_5") (pintype "passive"))
      (node (ref "Y1") (pin "1") (pinfunction "OSC1_1") (pintype "passive"))
    )
    (net (code "64") (name "Net-(U1-OSCOUT)") (class "Default")
      (node (ref "C14") (pin "2") (pinfunction "2_2") (pintype "passive"))
      (node (ref "U1") (pin "6") (pinfunction "OSCOUT_6") (pintype "passive"))
      (node (ref "Y1") (pin "2") (pinfunction "OSC2_2") (pintype "passive"))
    )
    (net (code "65") (name "Net-(U1-USB_DM)") (class "Default")
      (node (ref "R14") (pin "2") (pinfunction "2_2") (pintype "passive"))
      (node (ref "U1") (pin "32") (pinfunction "USB_DM_32") (pintype "passive"))
    )
    (net (code "66") (name "Net-(U1-USB_DP)") (class "Default")
      (node (ref "R15") (pin "2") (pinfunction "2_2") (pintype "passive"))
      (node (ref "U1") (pin "33") (pinfunction "USB_DP_33") (pintype "passive"))
    )
    (net (code "67") (name "Net-(U2-X)") (class "Default")
      (node (ref "C1") (pin "2") (pinfunction "2_2") (pintype "passive"))
      (node (ref "R1") (pin "1") (pinfunction "1_1") (pintype "passive"))
      (node (ref "R2") (pin "2") (pinfunction "2_2") (pintype "passive"))
      (node (ref "U2") (pin "13") (pinfunction "X_13") (pintype "passive"))
    )
    (net (code "68") (name "Net-(U2-X0)") (class "Default")
      (node (ref "C5") (pin "1") (pinfunction "1_1") (pintype "passive"))
      (node (ref "U2") (pin "12") (pinfunction "X0_12") (pintype "passive"))
      (node (ref "U3") (pin "12") (pinfunction "X0_12") (pintype "passive"))
      (node (ref "U4") (pin "12") (pinfunction "X0_12") (pintype "passive"))
      (node (ref "U5") (pin "12") (pinfunction "X0_12") (pintype "passive"))
    )
    (net (code "69") (name "Net-(U2-X1)") (class "Default")
      (node (ref "C6") (pin "1") (pinfunction "1_1") (pintype "passive"))
      (node (ref "U2") (pin "14") (pinfunction "X1_14") (pintype "passive"))
      (node (ref "U3") (pin "14") (pinfunction "X1_14") (pintype "passive"))
      (node (ref "U4") (pin "14") (pinfunction "X1_14") (pintype "passive"))
      (node (ref "U5") (pin "14") (pinfunction "X1_14") (pintype "passive"))
    )
    (net (code "70") (name "Net-(U2-X2)") (class "Default")
      (node (ref "C7") (pin "1") (pinfunction "1_1") (pintype "passive"))
      (node (ref "U2") (pin "15") (pinfunction "X2_15") (pintype "passive"))
      (node (ref "U3") (pin "15") (pinfunction "X2_15") (pintype "passive"))
      (node (ref "U4") (pin "15") (pinfunction "X2_15") (pintype "passive"))
      (node (ref "U5") (pin "15") (pinfunction "X2_15") (pintype "passive"))
    )
    (net (code "71") (name "Net-(U2-X3)") (class "Default")
      (node (ref "C8") (pin "1") (pinfunction "1_1") (pintype "passive"))
      (node (ref "U2") (pin "11") (pinfunction "X3_11") (pintype "passive"))
      (node (ref "U3") (pin "11") (pinfunction "X3_11") (pintype "passive"))
      (node (ref "U4") (pin "11") (pinfunction "X3_11") (pintype "passive"))
      (node (ref "U5") (pin "11") (pinfunction "X3_11") (pintype "passive"))
    )
    (net (code "72") (name "Net-(U3-X)") (class "Default")
      (node (ref "C2") (pin "2") (pinfunction "2_2") (pintype "passive"))
      (node (ref "R3") (pin "1") (pinfunction "1_1") (pintype "passive"))
      (node (ref "R4") (pin "2") (pinfunction "2_2") (pintype "passive"))
      (node (ref "U3") (pin "13") (pinfunction "X_13") (pintype "passive"))
    )
    (net (code "73") (name "Net-(U4-X)") (class "Default")
      (node (ref "C3") (pin "2") (pinfunction "2_2") (pintype "passive"))
      (node (ref "R5") (pin "1") (pinfunction "1_1") (pintype "passive"))
      (node (ref "R6") (pin "2") (pinfunction "2_2") (pintype "passive"))
      (node (ref "U4") (pin "13") (pinfunction "X_13") (pintype "passive"))
    )
    (net (code "74") (name "Net-(U5-X)") (class "Default")
      (node (ref "C4") (pin "2") (pinfunction "2_2") (pintype "passive"))
      (node (ref "R7") (pin "1") (pinfunction "1_1") (pintype "passive"))
      (node (ref "R8") (pin "2") (pinfunction "2_2") (pintype "passive"))
      (node (ref "U5") (pin "13") (pinfunction "X_13") (pintype "passive"))
    )
    (net (code "75") (name "unconnected-(J1-R-Pad2)") (class "Default")
      (node (ref "J1") (pin "2") (pinfunction "R_2") (pintype "passive"))
    )
    (net (code "76") (name "unconnected-(J2-R-Pad2)") (class "Default")
      (node (ref "J2") (pin "2") (pinfunction "R_2") (pintype "passive"))
    )
    (net (code "77") (name "unconnected-(J3-R-Pad2)") (class "Default")
      (node (ref "J3") (pin "2") (pinfunction "R_2") (pintype "passive"))
    )
    (net (code "78") (name "unconnected-(J4-R-Pad2)") (class "Default")
      (node (ref "J4") (pin "2") (pinfunction "R_2") (pintype "passive"))
    )
    (net (code "79") (name "unconnected-(P0-ID-Pad4)") (class "Default")
      (node (ref "P0") (pin "4") (pinfunction "ID_4") (pintype "passive"))
    )
    (net (code "80") (name "unconnected-(U1-PA8-Pad29)") (class "Default")
      (node (ref "U1") (pin "29") (pinfunction "PA8_29") (pintype "passive"))
    )
    (net (code "81") (name "unconnected-(U1-PA15-Pad38)") (class "Default")
      (node (ref "U1") (pin "38") (pinfunction "PA15_38") (pintype "passive"))
    )
    (net (code "82") (name "unconnected-(U1-PC13-Pad2)") (class "Default")
      (node (ref "U1") (pin "2") (pinfunction "PC13_2") (pintype "passive"))
    )
    (net (code "83") (name "unconnected-(U1-PC14-Pad3)") (class "Default")
      (node (ref "U1") (pin "3") (pinfunction "PC14_3") (pintype "passive"))
    )
    (net (code "84") (name "unconnected-(U1-PC15-Pad4)") (class "Default")
      (node (ref "U1") (pin "4") (pinfunction "PC15_4") (pintype "passive"))
    )
    (net (code "85") (name "unconnected-(U1-VBAT-Pad1)") (class "Default")
      (node (ref "U1") (pin "1") (pinfunction "VBAT_1") (pintype "passive"))
    )
    (net (code "86") (name "unconnected-(U2-NC-Pad7)") (class "Default")
      (node (ref "U2") (pin "7") (pinfunction "NC_7") (pintype "passive"))
    )
    (net (code "87") (name "unconnected-(U3-NC-Pad7)") (class "Default")
      (node (ref "U3") (pin "7") (pinfunction "NC_7") (pintype "passive"))
    )
    (net (code "88") (name "unconnected-(U4-NC-Pad7)") (class "Default")
      (node (ref "U4") (pin "7") (pinfunction "NC_7") (pintype "passive"))
    )
    (net (code "89") (name "unconnected-(U5-NC-Pad7)") (class "Default")
      (node (ref "U5") (pin "7") (pinfunction "NC_7") (pintype "passive"))
    )
  )
)
